# 02_Power.net
KiCad netlist of a schematic drawn in Altium Designer
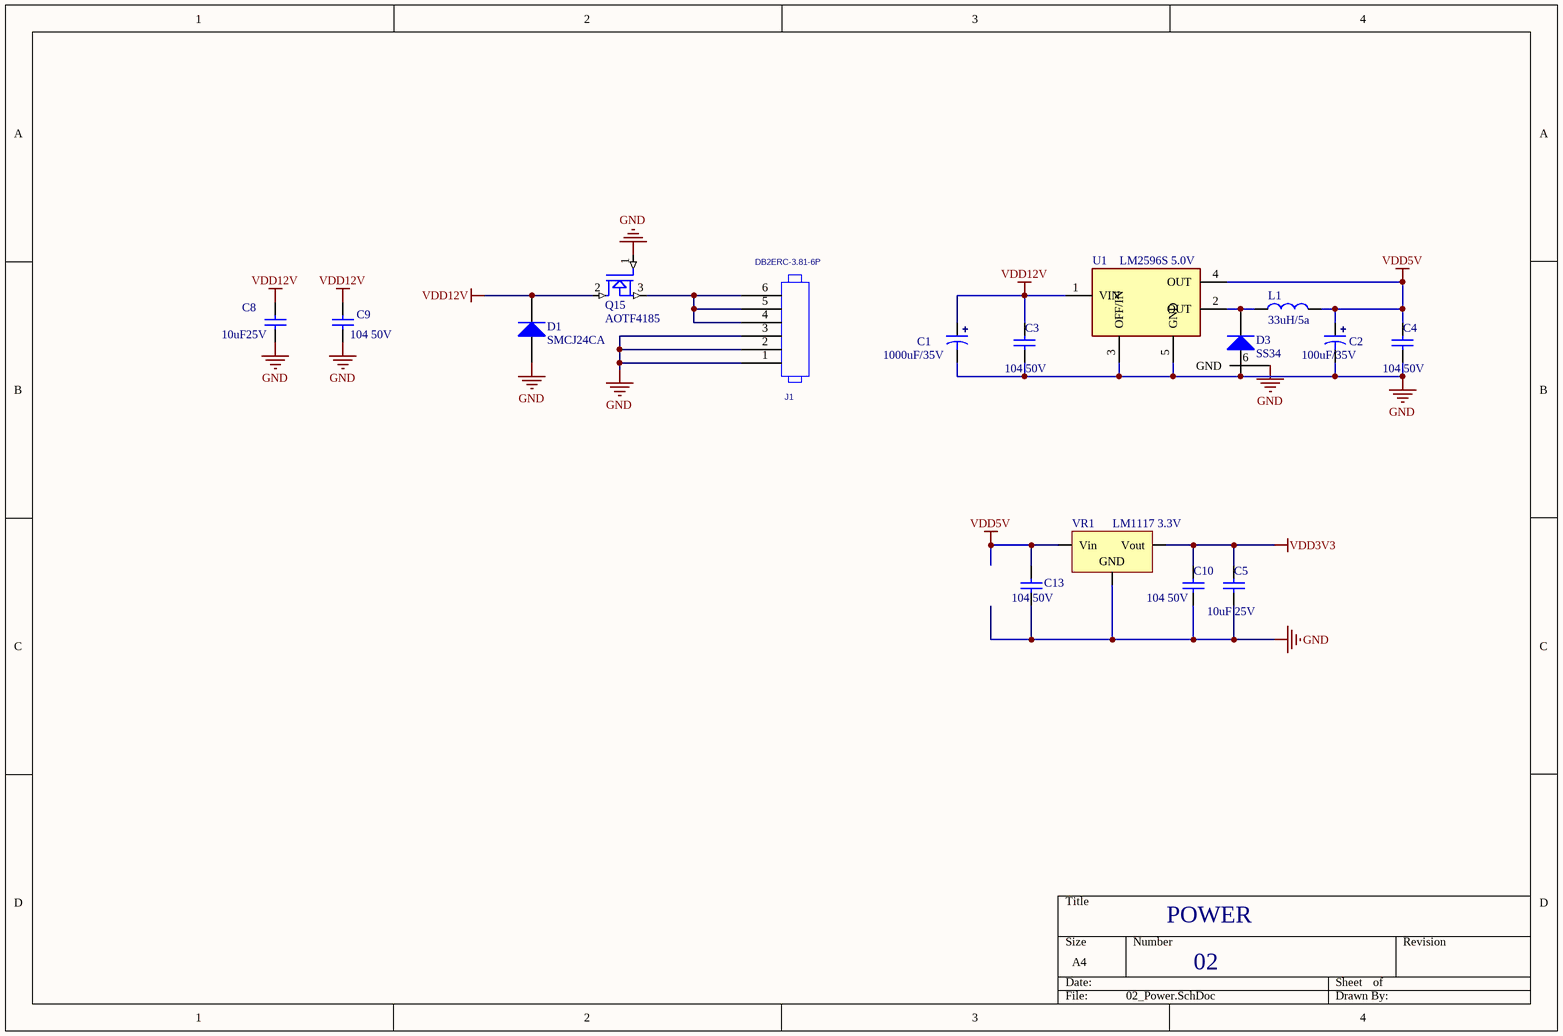
[diagram p0: 02_Power.SchDoc]

(export (version "E")
  (design (tool "Eeschema 10.0.6"))
  (components
    (comp (ref "C1")
      (value "1000uF/35V")
      (footprint "10*16")
      (description "电解电容")
      (libsource (lib "XiaoyI") (part "CAP2"))
    )
    (comp (ref "C2")
      (value "100uF/35V")
      (footprint "6*8")
      (description "电解电容")
      (libsource (lib "XiaoyI") (part "CAP2"))
    )
    (comp (ref "C3")
      (value "104 50V")
      (footprint "SMD-0603C")
      (description "贴片电容 10%")
      (libsource (lib "XiaoyI") (part "CAP4"))
    )
    (comp (ref "C4")
      (value "104 50V")
      (footprint "SMD-0603C")
      (description "贴片电容 10%")
      (libsource (lib "XiaoyI") (part "CAP4"))
    )
    (comp (ref "C5")
      (value "10uF 25V")
      (footprint "SMD-0805C")
      (description "贴片电容 20%")
      (libsource (lib "XiaoyI") (part "CAP4"))
    )
    (comp (ref "C8")
      (value "10uF25V")
      (footprint "SMD-0805C")
      (description "贴片电容 10%")
      (libsource (lib "XiaoyI") (part "CAP4"))
    )
    (comp (ref "C9")
      (value "104 50V")
      (footprint "SMD-0603C")
      (description "贴片电容 10%")
      (libsource (lib "XiaoyI") (part "CAP4"))
    )
    (comp (ref "C10")
      (value "104 50V")
      (footprint "SMD-0603C")
      (description "贴片电容 10%")
      (libsource (lib "XiaoyI") (part "CAP4"))
    )
    (comp (ref "C13")
      (value "104 50V")
      (footprint "SMD-0603C")
      (description "贴片电容 10%")
      (libsource (lib "XiaoyI") (part "CAP4"))
    )
    (comp (ref "D1")
      (value "SMCJ24CA")
      (footprint "Pcblib_20110825:SMC")
      (libsource (lib "Sch_library") (part "DIODE"))
    )
    (comp (ref "D3") (value "SS34") (footprint "SMA") (libsource (lib "Sch_library") (part "DIODE")))
    (comp (ref "J1")
      (value "DB2ERC-3.81-6P")
      (footprint "VH-AW-3.96*6P")
      (fields (field (name "Comment") "HEADER_6"))
      (libsource (lib "liujingtao_V1.0") (part "HEADER_6"))
    )
    (comp (ref "L1") (value "33uH/5a") (footprint "CDRH-127") (libsource (lib "Sch_library") (part "IND")))
    (comp (ref "Q15")
      (value "AOTF4185")
      (footprint "Pcblib_20110825:to220")
      (description "MOSFET N")
      (libsource (lib "XiaoyI") (part "MOSFET N"))
    )
    (comp (ref "U1")
      (value "LM2596S 5.0V")
      (footprint "TO-263-5")
      (libsource (lib "Sch_library") (part "LM2596"))
    )
    (comp (ref "VR1")
      (value "LM1117 3.3V")
      (footprint "SOT223")
      (description "三端稳压器")
      (libsource (lib "XiaoyI") (part "LM1117"))
    )
  )
  (nets
    (net (code "1") (name "GND") (class "Default")
      (node (ref "C1") (pin "2") (pinfunction "2_2") (pintype "passive"))
      (node (ref "C10") (pin "1") (pinfunction "1_1") (pintype "passive"))
      (node (ref "C13") (pin "1") (pinfunction "1_1") (pintype "passive"))
      (node (ref "C2") (pin "2") (pinfunction "2_2") (pintype "passive"))
      (node (ref "C3") (pin "1") (pinfunction "1_1") (pintype "passive"))
      (node (ref "C4") (pin "1") (pinfunction "1_1") (pintype "passive"))
      (node (ref "C5") (pin "1") (pinfunction "1_1") (pintype "passive"))
      (node (ref "C8") (pin "1") (pinfunction "1_1") (pintype "passive"))
      (node (ref "C9") (pin "1") (pinfunction "1_1") (pintype "passive"))
      (node (ref "D1") (pin "1") (pinfunction "A_1") (pintype "passive"))
      (node (ref "D3") (pin "1") (pinfunction "A_1") (pintype "passive"))
      (node (ref "J1") (pin "1") (pinfunction "1_1") (pintype "passive"))
      (node (ref "J1") (pin "2") (pinfunction "2_2") (pintype "passive"))
      (node (ref "J1") (pin "3") (pinfunction "3_3") (pintype "passive"))
      (node (ref "Q15") (pin "1") (pinfunction "G_1") (pintype "input"))
      (node (ref "U1") (pin "3") (pinfunction "OFF/IN_3") (pintype "passive"))
      (node (ref "U1") (pin "5") (pinfunction "GND_5") (pintype "passive"))
      (node (ref "U1") (pin "6") (pinfunction "GND_6") (pintype "passive"))
      (node (ref "VR1") (pin "1") (pinfunction "GND_1") (pintype "passive"))
    )
    (net (code "2") (name "Net-(D3-K)") (class "Default")
      (node (ref "D3") (pin "2") (pinfunction "K_2") (pintype "passive"))
      (node (ref "L1") (pin "1") (pinfunction "1_1") (pintype "passive"))
      (node (ref "U1") (pin "2") (pinfunction "OUT_2") (pintype "passive"))
    )
    (net (code "3") (name "Net-(Q15-S)") (class "Default")
      (node (ref "J1") (pin "4") (pinfunction "4_4") (pintype "passive"))
      (node (ref "J1") (pin "5") (pinfunction "5_5") (pintype "passive"))
      (node (ref "J1") (pin "6") (pinfunction "6_6") (pintype "passive"))
      (node (ref "Q15") (pin "3") (pinfunction "S_3") (pintype "output"))
    )
    (net (code "4") (name "VDD3V3") (class "Default")
      (node (ref "C10") (pin "2") (pinfunction "2_2") (pintype "passive"))
      (node (ref "C5") (pin "2") (pinfunction "2_2") (pintype "passive"))
      (node (ref "VR1") (pin "2") (pinfunction "Vout_2") (pintype "passive"))
    )
    (net (code "5") (name "VDD5V") (class "Default")
      (node (ref "C13") (pin "2") (pinfunction "2_2") (pintype "passive"))
      (node (ref "C2") (pin "1") (pinfunction "1_1") (pintype "passive"))
      (node (ref "C4") (pin "2") (pinfunction "2_2") (pintype "passive"))
      (node (ref "L1") (pin "2") (pinfunction "2_2") (pintype "passive"))
      (node (ref "U1") (pin "4") (pinfunction "OUT_4") (pintype "passive"))
      (node (ref "VR1") (pin "3") (pinfunction "Vin_3") (pintype "passive"))
    )
    (net (code "6") (name "VDD12V") (class "Default")
      (node (ref "C1") (pin "1") (pinfunction "1_1") (pintype "passive"))
      (node (ref "C3") (pin "2") (pinfunction "2_2") (pintype "passive"))
      (node (ref "C8") (pin "2") (pinfunction "2_2") (pintype "passive"))
      (node (ref "C9") (pin "2") (pinfunction "2_2") (pintype "passive"))
      (node (ref "D1") (pin "2") (pinfunction "K_2") (pintype "passive"))
      (node (ref "Q15") (pin "2") (pinfunction "D_2") (pintype "input"))
      (node (ref "U1") (pin "1") (pinfunction "VIN_1") (pintype "passive"))
    )
  )
)
